# SCH_555-Circuit_2025-03-12.net
KiCad netlist of a schematic drawn in EasyEDA
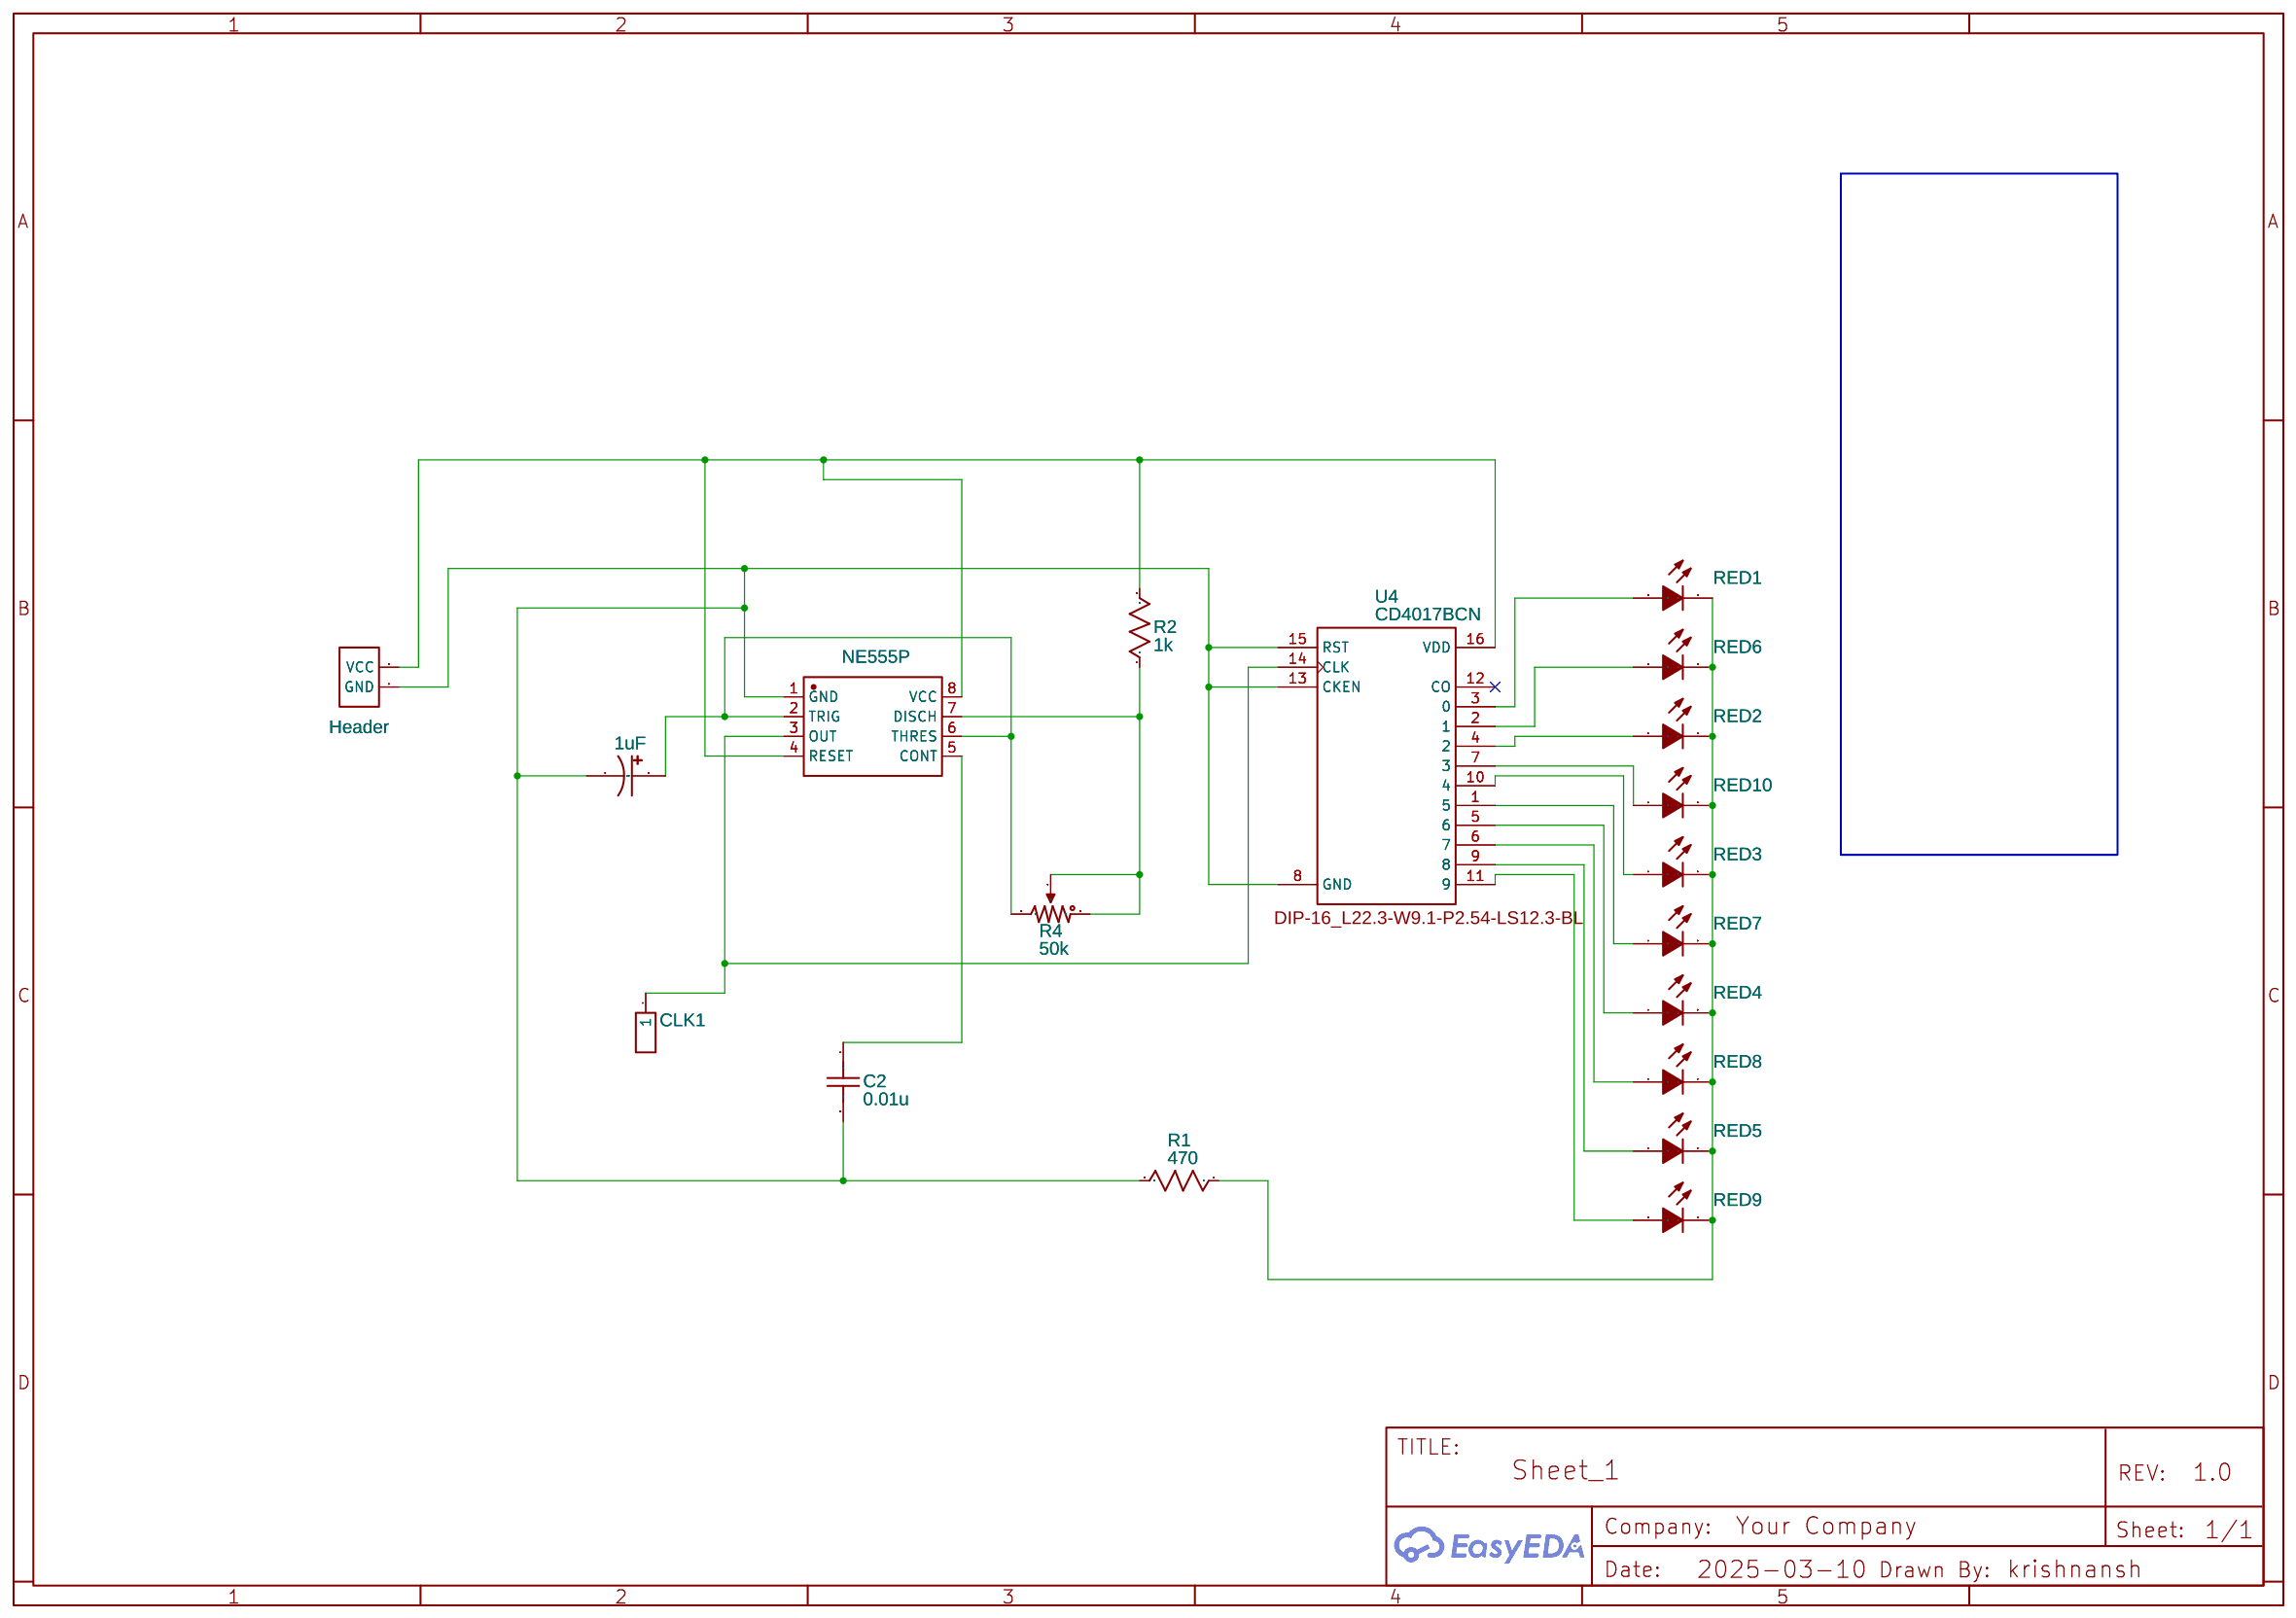
[diagram p0: schematic sheet]

(export (version "E")
  (design (tool "Eeschema 10.0.6"))
  (components
    (comp (ref "C1")
      (value "1uF")
      (fields (field (name "Manufacturer Part") "UVZ1H010MDD") (field (name "Manufacturer") "Nichicon(尼吉康)"))
      (libsource (lib "") (part "UVZ1H010MDD"))
    )
    (comp (ref "C2") (value "0.01u") (libsource (lib "") (part "C_0603_US")))
    (comp (ref "CLK1")
      (value "C81276")
      (fields
        (field (name "Manufacturer Part") "2.54-1*1P针")
        (field (name "Manufacturer") "BOOMELE(Boom Precision Elec)")
      )
      (libsource (lib "") (part "Header-Male-2.54_1x1"))
    )
    (comp (ref "H1") (value "Header") (libsource (lib "") (part "HEADER-FEMALE-2.54_1X2")))
    (comp (ref "R1")
      (value "470")
      (fields (field (name "Manufacturer Part") "?"))
      (libsource (lib "") (part "Resistor"))
    )
    (comp (ref "R2")
      (value "1k")
      (fields (field (name "Manufacturer Part") "?"))
      (libsource (lib "") (part "Resistor_1"))
    )
    (comp (ref "R4")
      (value "50k")
      (fields (field (name "Manufacturer Part") "?"))
      (libsource (lib "") (part "Potentiometer"))
    )
    (comp (ref "RED1") (value "LED_5MM") (libsource (lib "") (part "LED_5MM")))
    (comp (ref "RED2") (value "LED_5MM") (libsource (lib "") (part "LED_5MM")))
    (comp (ref "RED3") (value "LED_5MM") (libsource (lib "") (part "LED_5MM")))
    (comp (ref "RED4") (value "LED_5MM") (libsource (lib "") (part "LED_5MM")))
    (comp (ref "RED5") (value "LED_5MM") (libsource (lib "") (part "LED_5MM")))
    (comp (ref "RED6") (value "LED_5MM") (libsource (lib "") (part "LED_5MM")))
    (comp (ref "RED7") (value "LED_5MM") (libsource (lib "") (part "LED_5MM")))
    (comp (ref "RED8") (value "LED_5MM") (libsource (lib "") (part "LED_5MM")))
    (comp (ref "RED9") (value "LED_5MM") (libsource (lib "") (part "LED_5MM")))
    (comp (ref "RED10") (value "LED_5MM") (libsource (lib "") (part "LED_5MM")))
    (comp (ref "U2")
      (value "NE555P")
      (fields (field (name "Manufacturer") "TI(德州仪器)"))
      (libsource (lib "") (part "NE555P"))
    )
    (comp (ref "U4") (value "CD4017BCN") (libsource (lib "") (part "CD4017BCN")))
  )
  (nets
    (net (code "1") (name "Net-(H1-GND)") (class "Default")
      (node (ref "C1") (pin "2") (pinfunction "2_2") (pintype "unspecified"))
      (node (ref "C2") (pin "2") (pinfunction "2_2") (pintype "unspecified"))
      (node (ref "H1") (pin "2") (pinfunction "GND_2") (pintype "unspecified"))
      (node (ref "R1") (pin "2") (pinfunction "2_2") (pintype "unspecified"))
      (node (ref "U2") (pin "1") (pinfunction "GND_1") (pintype "unspecified"))
      (node (ref "U4") (pin "13") (pinfunction "CKEN_13") (pintype "unspecified"))
      (node (ref "U4") (pin "15") (pinfunction "RST_15") (pintype "unspecified"))
      (node (ref "U4") (pin "8") (pinfunction "GND_8") (pintype "passive"))
    )
    (net (code "2") (name "Net-(H1-VCC)") (class "Default")
      (node (ref "H1") (pin "1") (pinfunction "VCC_1") (pintype "unspecified"))
      (node (ref "R2") (pin "2") (pinfunction "2_2") (pintype "unspecified"))
      (node (ref "U2") (pin "4") (pinfunction "RESET_4") (pintype "unspecified"))
      (node (ref "U2") (pin "8") (pinfunction "VCC_8") (pintype "unspecified"))
      (node (ref "U4") (pin "16") (pinfunction "VDD_16") (pintype "passive"))
    )
    (net (code "3") (name "Net-(R4-2)") (class "Default")
      (node (ref "R2") (pin "1") (pinfunction "1_1") (pintype "unspecified"))
      (node (ref "R4") (pin "2") (pinfunction "3_2") (pintype "unspecified"))
      (node (ref "R4") (pin "3") (pinfunction "2_3") (pintype "unspecified"))
      (node (ref "U2") (pin "7") (pinfunction "DISCH_7") (pintype "unspecified"))
    )
    (net (code "4") (name "Net-(RED1-A)") (class "Default")
      (node (ref "RED1") (pin "1") (pinfunction "A_1") (pintype "input"))
      (node (ref "U4") (pin "3") (pinfunction "0_3") (pintype "output"))
    )
    (net (code "5") (name "Net-(RED1-K)") (class "Default")
      (node (ref "R1") (pin "1") (pinfunction "1_1") (pintype "unspecified"))
      (node (ref "RED1") (pin "2") (pinfunction "K_2") (pintype "input"))
      (node (ref "RED10") (pin "2") (pinfunction "K_2") (pintype "input"))
      (node (ref "RED2") (pin "2") (pinfunction "K_2") (pintype "input"))
      (node (ref "RED3") (pin "2") (pinfunction "K_2") (pintype "input"))
      (node (ref "RED4") (pin "2") (pinfunction "K_2") (pintype "input"))
      (node (ref "RED5") (pin "2") (pinfunction "K_2") (pintype "input"))
      (node (ref "RED6") (pin "2") (pinfunction "K_2") (pintype "input"))
      (node (ref "RED7") (pin "2") (pinfunction "K_2") (pintype "input"))
      (node (ref "RED8") (pin "2") (pinfunction "K_2") (pintype "input"))
      (node (ref "RED9") (pin "2") (pinfunction "K_2") (pintype "input"))
    )
    (net (code "6") (name "Net-(RED2-A)") (class "Default")
      (node (ref "RED2") (pin "1") (pinfunction "A_1") (pintype "input"))
      (node (ref "U4") (pin "4") (pinfunction "2_4") (pintype "output"))
    )
    (net (code "7") (name "Net-(RED3-A)") (class "Default")
      (node (ref "RED3") (pin "1") (pinfunction "A_1") (pintype "input"))
      (node (ref "U4") (pin "10") (pinfunction "4_10") (pintype "output"))
    )
    (net (code "8") (name "Net-(RED4-A)") (class "Default")
      (node (ref "RED4") (pin "1") (pinfunction "A_1") (pintype "input"))
      (node (ref "U4") (pin "5") (pinfunction "6_5") (pintype "output"))
    )
    (net (code "9") (name "Net-(RED5-A)") (class "Default")
      (node (ref "RED5") (pin "1") (pinfunction "A_1") (pintype "input"))
      (node (ref "U4") (pin "9") (pinfunction "8_9") (pintype "output"))
    )
    (net (code "10") (name "Net-(RED6-A)") (class "Default")
      (node (ref "RED6") (pin "1") (pinfunction "A_1") (pintype "input"))
      (node (ref "U4") (pin "2") (pinfunction "1_2") (pintype "output"))
    )
    (net (code "11") (name "Net-(RED7-A)") (class "Default")
      (node (ref "RED7") (pin "1") (pinfunction "A_1") (pintype "input"))
      (node (ref "U4") (pin "1") (pinfunction "5_1") (pintype "output"))
    )
    (net (code "12") (name "Net-(RED8-A)") (class "Default")
      (node (ref "RED8") (pin "1") (pinfunction "A_1") (pintype "input"))
      (node (ref "U4") (pin "6") (pinfunction "7_6") (pintype "output"))
    )
    (net (code "13") (name "Net-(RED9-A)") (class "Default")
      (node (ref "RED9") (pin "1") (pinfunction "A_1") (pintype "input"))
      (node (ref "U4") (pin "11") (pinfunction "9_11") (pintype "output"))
    )
    (net (code "14") (name "Net-(RED10-A)") (class "Default")
      (node (ref "RED10") (pin "1") (pinfunction "A_1") (pintype "input"))
      (node (ref "U4") (pin "7") (pinfunction "3_7") (pintype "output"))
    )
    (net (code "15") (name "Net-(U2-CONT)") (class "Default")
      (node (ref "C2") (pin "1") (pinfunction "1_1") (pintype "unspecified"))
      (node (ref "U2") (pin "5") (pinfunction "CONT_5") (pintype "unspecified"))
    )
    (net (code "16") (name "Net-(U2-OUT)") (class "Default")
      (node (ref "CLK1") (pin "1") (pinfunction "1_1") (pintype "unspecified"))
      (node (ref "U2") (pin "3") (pinfunction "OUT_3") (pintype "unspecified"))
      (node (ref "U4") (pin "14") (pinfunction "CLK_14") (pintype "unspecified"))
    )
    (net (code "17") (name "Net-(U2-THRES)") (class "Default")
      (node (ref "C1") (pin "1") (pinfunction "1_1") (pintype "unspecified"))
      (node (ref "R4") (pin "1") (pinfunction "1_1") (pintype "unspecified"))
      (node (ref "U2") (pin "2") (pinfunction "TRIG_2") (pintype "unspecified"))
      (node (ref "U2") (pin "6") (pinfunction "THRES_6") (pintype "unspecified"))
    )
    (net (code "18") (name "unconnected-(U4-CO-Pad12)") (class "Default")
      (node (ref "U4") (pin "12") (pinfunction "CO_12") (pintype "output+no_connect"))
    )
  )
)
